# ControllerBoard.net
KiCad netlist of a schematic drawn in Altium Designer
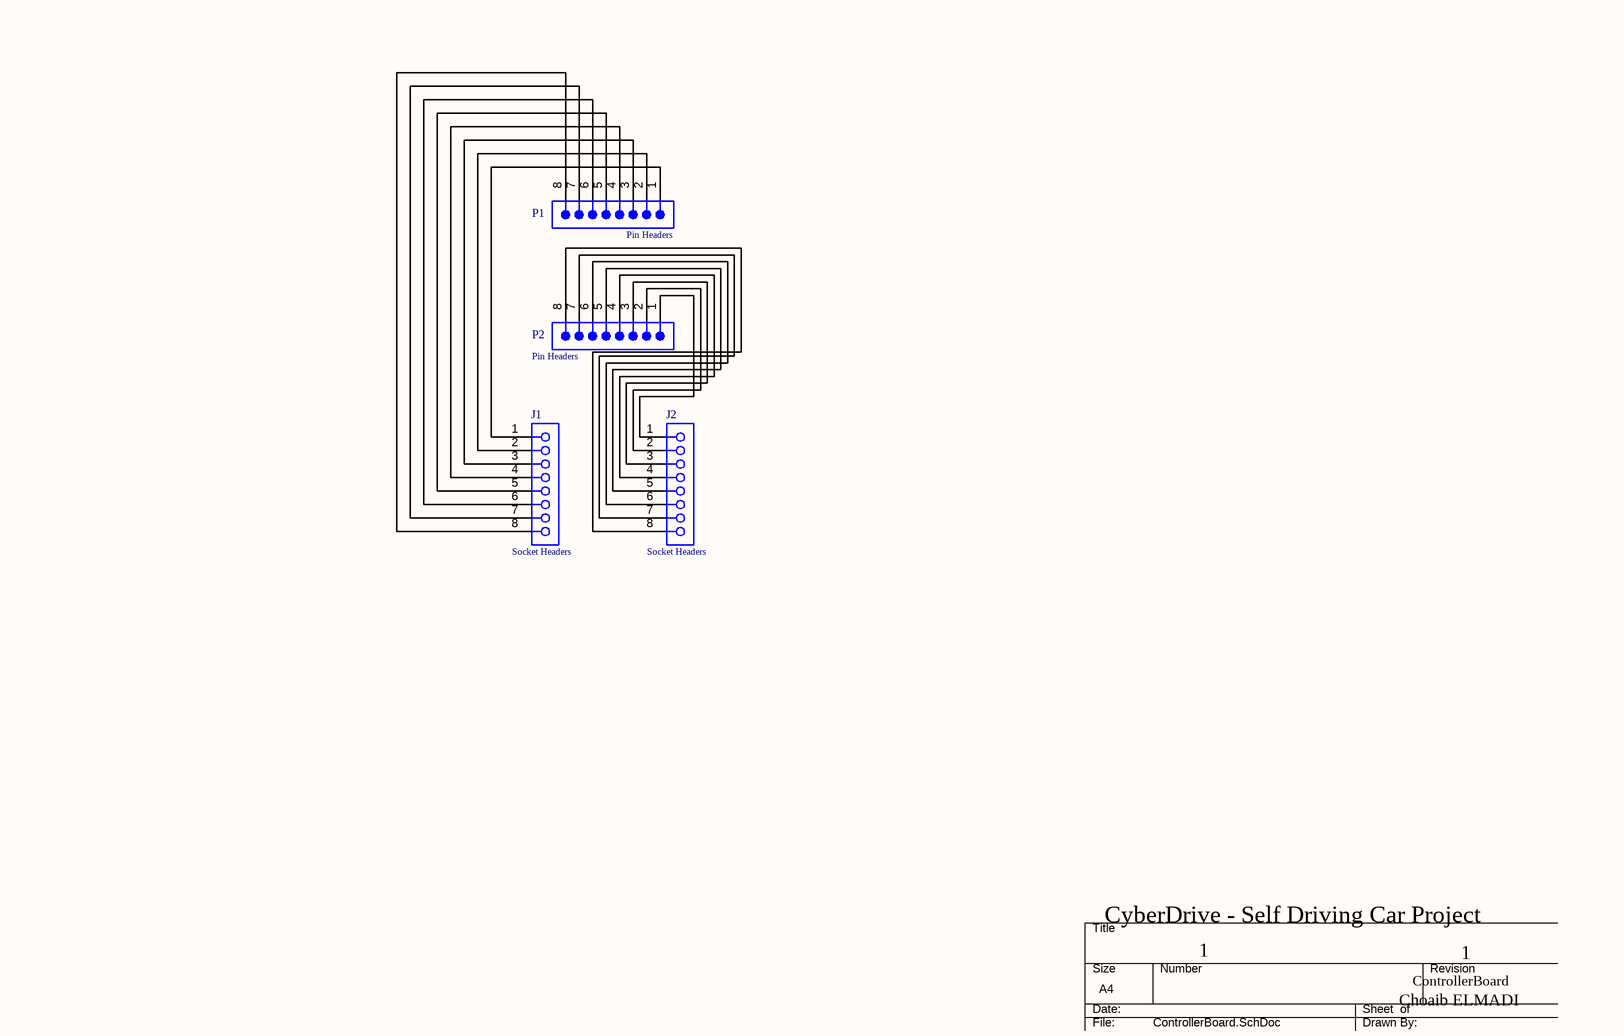
[diagram p0: ControllerBoard.SchDoc]

(export (version "E")
  (design (tool "Eeschema 10.0.6"))
  (components
    (comp (ref "J1")
      (value "Socket Headers")
      (footprint "61300811821")
      (libsource (lib "Altium Content Vault") (part "Header_Female_1R_08P"))
    )
    (comp (ref "J2")
      (value "Socket Headers")
      (footprint "61300811821")
      (libsource (lib "Altium Content Vault") (part "Header_Female_1R_08P"))
    )
    (comp (ref "P1")
      (value "Pin Headers")
      (footprint "61300811121")
      (libsource (lib "Altium Content Vault") (part "Header_Male_1R_08P"))
    )
    (comp (ref "P2")
      (value "Pin Headers")
      (footprint "61300811121")
      (libsource (lib "Altium Content Vault") (part "Header_Male_1R_08P"))
    )
  )
  (nets
    (net (code "1") (name "Net-(J1-Pad1)") (class "Default")
      (node (ref "J1") (pin "1") (pinfunction "1_1") (pintype "passive"))
      (node (ref "P1") (pin "1") (pinfunction "1_1") (pintype "passive"))
    )
    (net (code "2") (name "Net-(J1-Pad2)") (class "Default")
      (node (ref "J1") (pin "2") (pinfunction "2_2") (pintype "passive"))
      (node (ref "P1") (pin "2") (pinfunction "2_2") (pintype "passive"))
    )
    (net (code "3") (name "Net-(J1-Pad3)") (class "Default")
      (node (ref "J1") (pin "3") (pinfunction "3_3") (pintype "passive"))
      (node (ref "P1") (pin "3") (pinfunction "3_3") (pintype "passive"))
    )
    (net (code "4") (name "Net-(J1-Pad4)") (class "Default")
      (node (ref "J1") (pin "4") (pinfunction "4_4") (pintype "passive"))
      (node (ref "P1") (pin "4") (pinfunction "4_4") (pintype "passive"))
    )
    (net (code "5") (name "Net-(J1-Pad5)") (class "Default")
      (node (ref "J1") (pin "5") (pinfunction "5_5") (pintype "passive"))
      (node (ref "P1") (pin "5") (pinfunction "5_5") (pintype "passive"))
    )
    (net (code "6") (name "Net-(J1-Pad6)") (class "Default")
      (node (ref "J1") (pin "6") (pinfunction "6_6") (pintype "passive"))
      (node (ref "P1") (pin "6") (pinfunction "6_6") (pintype "passive"))
    )
    (net (code "7") (name "Net-(J1-Pad7)") (class "Default")
      (node (ref "J1") (pin "7") (pinfunction "7_7") (pintype "passive"))
      (node (ref "P1") (pin "7") (pinfunction "7_7") (pintype "passive"))
    )
    (net (code "8") (name "Net-(J1-Pad8)") (class "Default")
      (node (ref "J1") (pin "8") (pinfunction "8_8") (pintype "passive"))
      (node (ref "P1") (pin "8") (pinfunction "8_8") (pintype "passive"))
    )
    (net (code "9") (name "Net-(J2-Pad1)") (class "Default")
      (node (ref "J2") (pin "1") (pinfunction "1_1") (pintype "passive"))
      (node (ref "P2") (pin "1") (pinfunction "1_1") (pintype "passive"))
    )
    (net (code "10") (name "Net-(J2-Pad2)") (class "Default")
      (node (ref "J2") (pin "2") (pinfunction "2_2") (pintype "passive"))
      (node (ref "P2") (pin "2") (pinfunction "2_2") (pintype "passive"))
    )
    (net (code "11") (name "Net-(J2-Pad3)") (class "Default")
      (node (ref "J2") (pin "3") (pinfunction "3_3") (pintype "passive"))
      (node (ref "P2") (pin "3") (pinfunction "3_3") (pintype "passive"))
    )
    (net (code "12") (name "Net-(J2-Pad4)") (class "Default")
      (node (ref "J2") (pin "4") (pinfunction "4_4") (pintype "passive"))
      (node (ref "P2") (pin "4") (pinfunction "4_4") (pintype "passive"))
    )
    (net (code "13") (name "Net-(J2-Pad5)") (class "Default")
      (node (ref "J2") (pin "5") (pinfunction "5_5") (pintype "passive"))
      (node (ref "P2") (pin "5") (pinfunction "5_5") (pintype "passive"))
    )
    (net (code "14") (name "Net-(J2-Pad6)") (class "Default")
      (node (ref "J2") (pin "6") (pinfunction "6_6") (pintype "passive"))
      (node (ref "P2") (pin "6") (pinfunction "6_6") (pintype "passive"))
    )
    (net (code "15") (name "Net-(J2-Pad7)") (class "Default")
      (node (ref "J2") (pin "7") (pinfunction "7_7") (pintype "passive"))
      (node (ref "P2") (pin "7") (pinfunction "7_7") (pintype "passive"))
    )
    (net (code "16") (name "Net-(J2-Pad8)") (class "Default")
      (node (ref "J2") (pin "8") (pinfunction "8_8") (pintype "passive"))
      (node (ref "P2") (pin "8") (pinfunction "8_8") (pintype "passive"))
    )
  )
)
